# AU0003A.net
KiCad netlist of a schematic drawn in Altium Designer
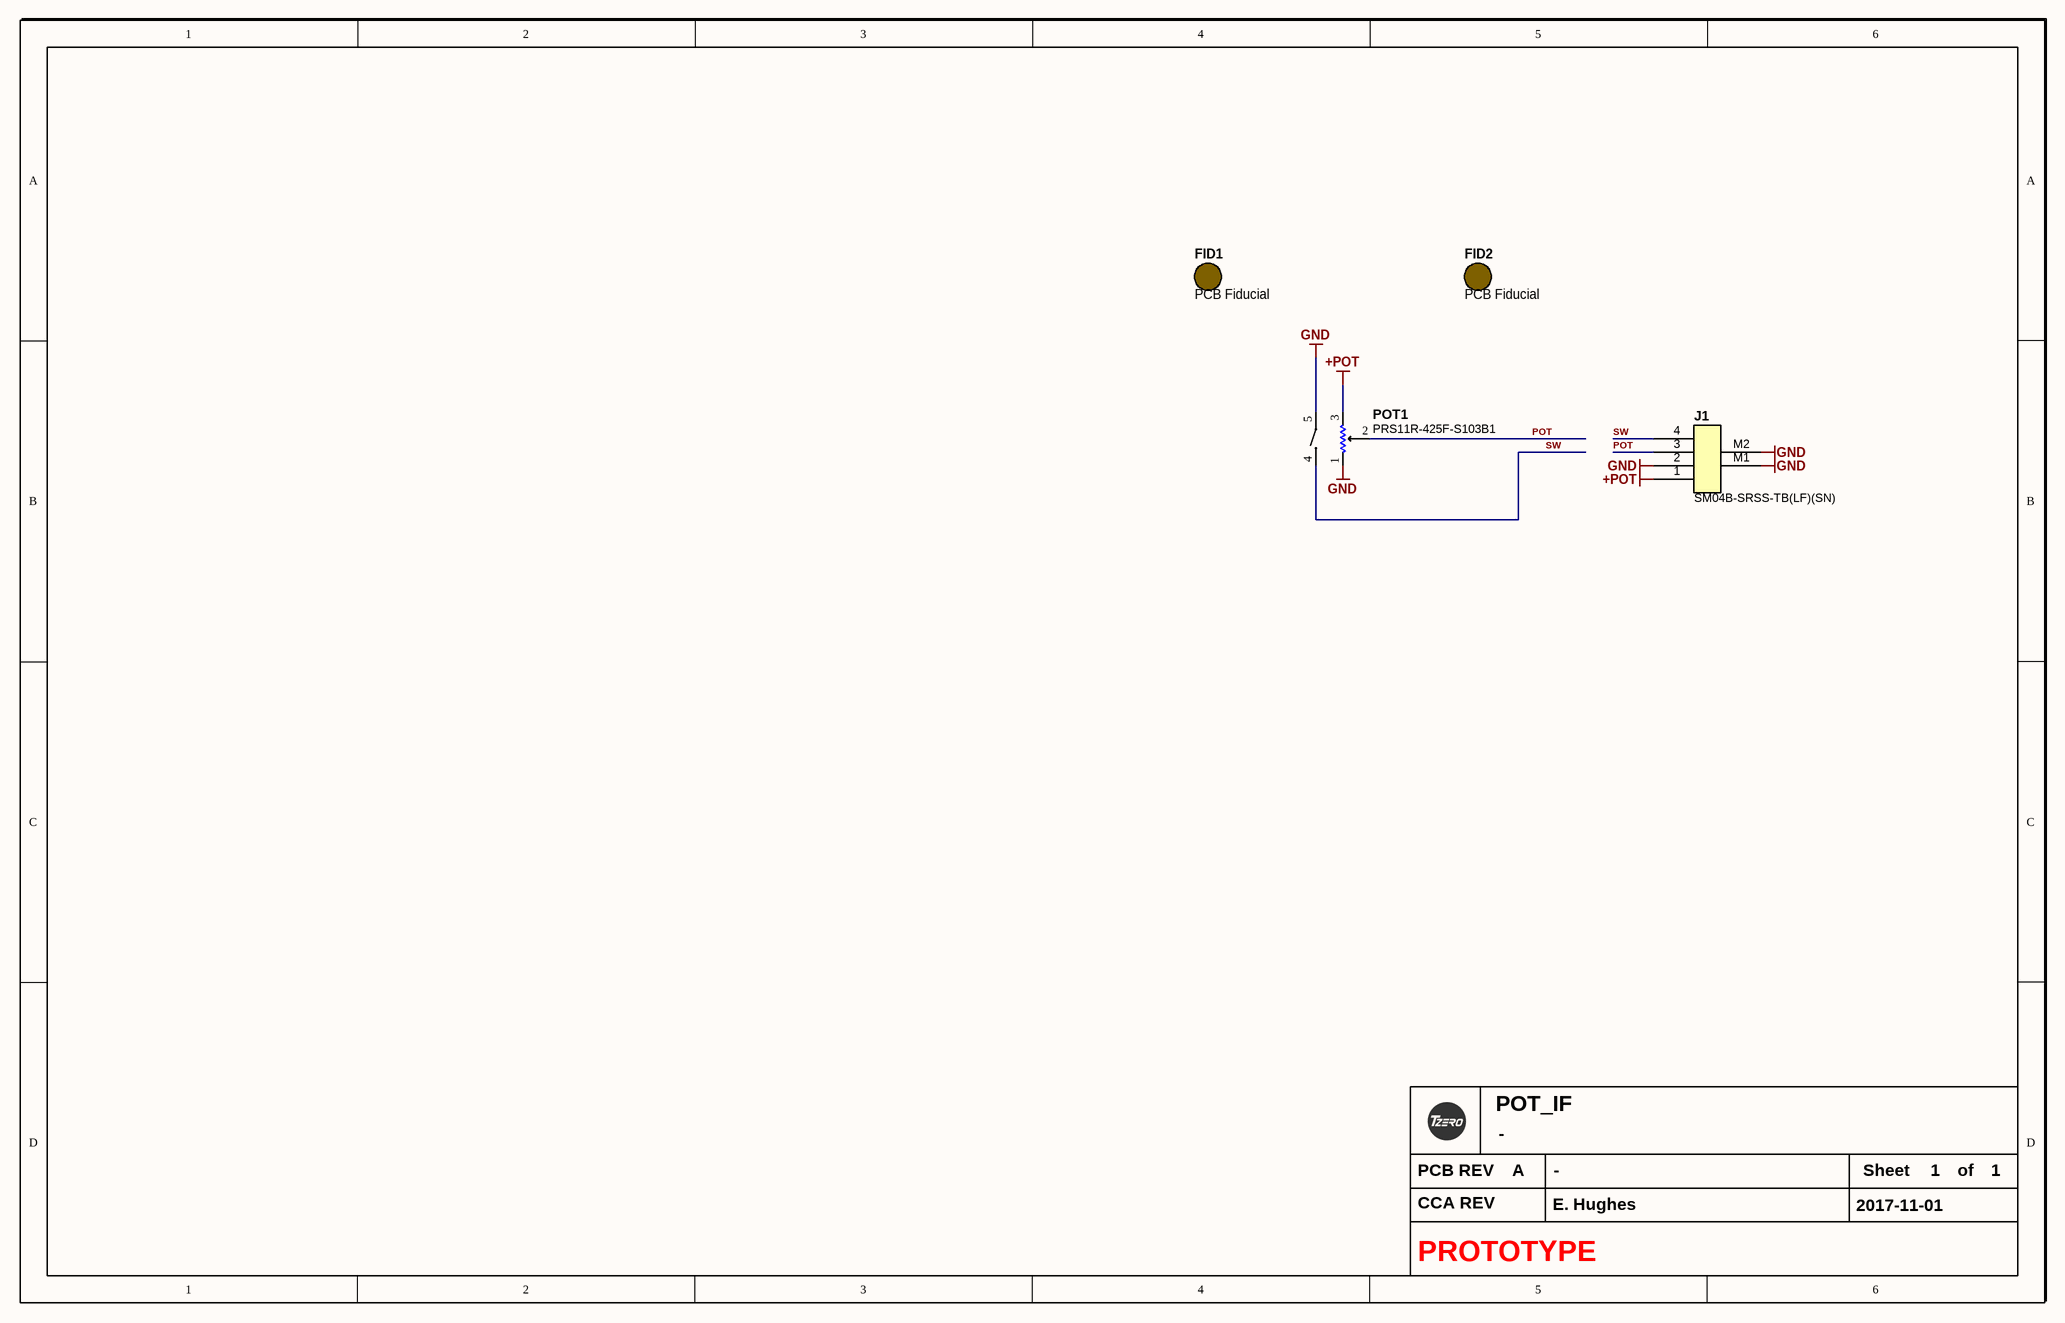
[diagram p0: AU0003A.SchDoc]

(export (version "E")
  (design (tool "Eeschema 10.0.6"))
  (components
    (comp (ref "FID1")
      (value "PCB Fiducial")
      (footprint "Fiducial 1mm - 2mm")
      (libsource (lib "eFiducial") (part "Fiducial"))
    )
    (comp (ref "FID2")
      (value "PCB Fiducial")
      (footprint "Fiducial 1mm - 2mm")
      (libsource (lib "eFiducial") (part "Fiducial"))
    )
    (comp (ref "J1")
      (value "SM04B-SRSS-TB(LF)(SN)")
      (footprint "SM04B-SRSS-TB(LF)(SN)")
      (description "Conn Shrouded Header HDR 4 POS 1mm Solder RA SMD T/R")
      (fields (field (name "MANUFACTURER") "JST"))
      (libsource (lib "eConnector_JST_SM") (part "SM04B-SRSS-TB(LF)(SN)"))
    )
    (comp (ref "POT1")
      (value "PRS11R-425F-S103B1")
      (footprint "PRS11R425FS103B1")
      (description "10k Pot w/ Momentary Switch - 25mm Length")
      (fields (field (name "MANUFACTURER") "Bourns"))
      (libsource (lib "ePotentiometer") (part "PRS11R-425F-S103B1"))
    )
  )
  (nets
    (net (code "1") (name "+POT") (class "Default")
      (node (ref "J1") (pin "1") (pinfunction "1_1") (pintype "passive"))
      (node (ref "POT1") (pin "3") (pinfunction "3_3") (pintype "passive"))
    )
    (net (code "2") (name "/POT") (class "Default")
      (node (ref "J1") (pin "3") (pinfunction "3_3") (pintype "passive"))
      (node (ref "POT1") (pin "2") (pinfunction "2_2") (pintype "passive"))
    )
    (net (code "3") (name "/SW") (class "Default")
      (node (ref "J1") (pin "4") (pinfunction "4_4") (pintype "passive"))
      (node (ref "POT1") (pin "4") (pinfunction "4_4") (pintype "passive"))
    )
    (net (code "4") (name "GND") (class "Default")
      (node (ref "J1") (pin "2") (pinfunction "2_2") (pintype "passive"))
      (node (ref "J1") (pin "M1") (pinfunction "M1_M1") (pintype "passive"))
      (node (ref "J1") (pin "M2") (pinfunction "M2_M2") (pintype "passive"))
      (node (ref "POT1") (pin "1") (pinfunction "1_1") (pintype "passive"))
      (node (ref "POT1") (pin "5") (pinfunction "5_5") (pintype "passive"))
    )
  )
)
